# multi-pcb-gps.net
KiCad netlist of a schematic drawn in EAGLE
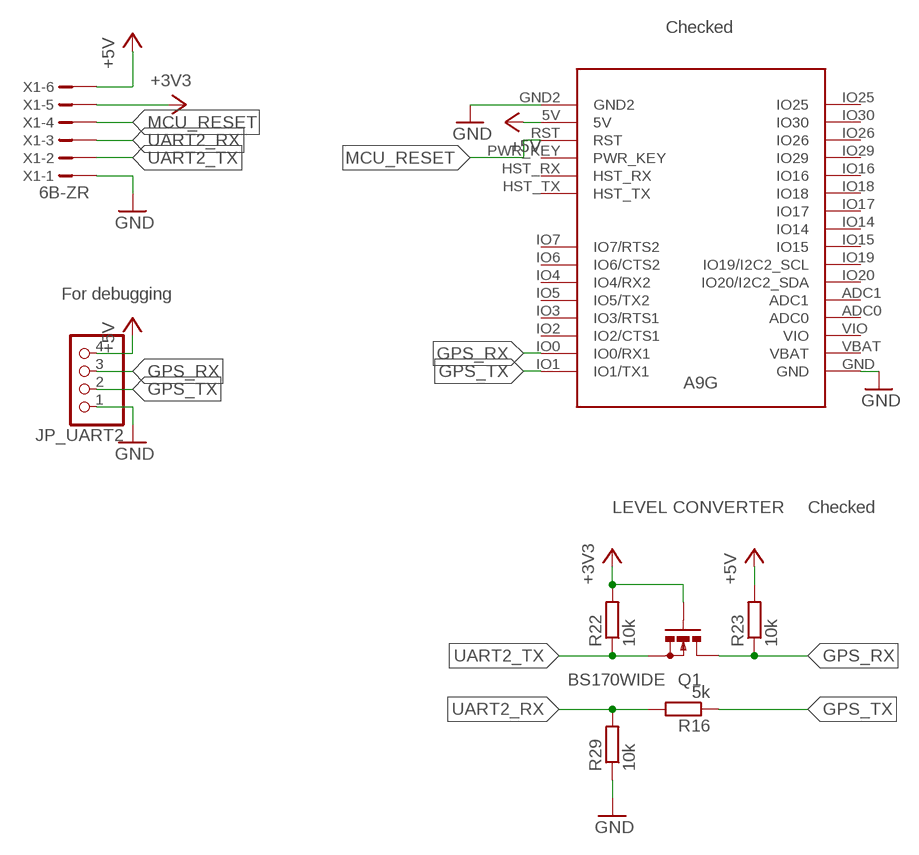
[diagram p0: schematic, sheet 1]

(export (version "E")
  (design (tool "Eeschema 10.0.6"))
  (components
    (comp (ref "JP_UART2")
      (value "PINHD-1X4")
      (footprint "eagle-import:1X04")
      (libsource (lib "eagle-import") (part "PINHD-1X4"))
    )
    (comp (ref "Q1")
      (value "BS170WIDE")
      (footprint "eagle-import:SOT54E2")
      (libsource (lib "eagle-import") (part "BS170WIDE"))
    )
    (comp (ref "R16")
      (value "5k")
      (footprint "eagle-import:0207_7")
      (libsource (lib "eagle-import") (part "R-EU_0207/7"))
    )
    (comp (ref "R22")
      (value "10k")
      (footprint "eagle-import:0207_7")
      (libsource (lib "eagle-import") (part "R-EU_0207/7"))
    )
    (comp (ref "R23")
      (value "10k")
      (footprint "eagle-import:0207_7")
      (libsource (lib "eagle-import") (part "R-EU_0207/7"))
    )
    (comp (ref "R29")
      (value "10k")
      (footprint "eagle-import:0207_7")
      (libsource (lib "eagle-import") (part "R-EU_0207/7"))
    )
    (comp (ref "U$6")
      (value "A9G")
      (footprint "eagle-import:A9G")
      (libsource (lib "eagle-import") (part "A9G"))
    )
    (comp (ref "X1")
      (value "6B-ZR")
      (footprint "eagle-import:B6B-ZR2.5")
      (libsource (lib "eagle-import") (part "?6B-ZR"))
    )
  )
  (nets
    (net (code "1") (name "+3V3") (class "Default")
      (node (ref "Q1") (pin "G") (pinfunction "G_G") (pintype "passive"))
      (node (ref "R22") (pin "2") (pinfunction "2_2") (pintype "passive"))
      (node (ref "X1") (pin "5") (pinfunction "1_5") (pintype "passive"))
    )
    (net (code "2") (name "+5V") (class "Default")
      (node (ref "JP_UART2") (pin "4") (pinfunction "4_4") (pintype "passive"))
      (node (ref "R23") (pin "2") (pinfunction "2_2") (pintype "passive"))
      (node (ref "U$6") (pin "5V") (pinfunction "5V_5V") (pintype "bidirectional"))
      (node (ref "X1") (pin "6") (pinfunction "1_6") (pintype "passive"))
    )
    (net (code "3") (name "GND") (class "Default")
      (node (ref "JP_UART2") (pin "1") (pinfunction "1_1") (pintype "passive"))
      (node (ref "R29") (pin "1") (pinfunction "1_1") (pintype "passive"))
      (node (ref "U$6") (pin "GND") (pinfunction "GND_GND") (pintype "bidirectional"))
      (node (ref "U$6") (pin "GND2") (pinfunction "GND2_GND2") (pintype "bidirectional"))
      (node (ref "X1") (pin "1") (pinfunction "1_1") (pintype "passive"))
    )
    (net (code "4") (name "GPS_RX") (class "Default")
      (node (ref "JP_UART2") (pin "3") (pinfunction "3_3") (pintype "passive"))
      (node (ref "Q1") (pin "D") (pinfunction "D_D") (pintype "passive"))
      (node (ref "R23") (pin "1") (pinfunction "1_1") (pintype "passive"))
      (node (ref "U$6") (pin "IO0") (pinfunction "IO0/RX1_IO0") (pintype "bidirectional"))
    )
    (net (code "5") (name "GPS_TX") (class "Default")
      (node (ref "JP_UART2") (pin "2") (pinfunction "2_2") (pintype "passive"))
      (node (ref "R16") (pin "1") (pinfunction "1_1") (pintype "passive"))
      (node (ref "U$6") (pin "IO1") (pinfunction "IO1/TX1_IO1") (pintype "bidirectional"))
    )
    (net (code "6") (name "MCU_RESET") (class "Default")
      (node (ref "U$6") (pin "RST") (pinfunction "RST_RST") (pintype "bidirectional"))
      (node (ref "X1") (pin "4") (pinfunction "1_4") (pintype "passive"))
    )
    (net (code "7") (name "UART2_RX") (class "Default")
      (node (ref "R16") (pin "2") (pinfunction "2_2") (pintype "passive"))
      (node (ref "R29") (pin "2") (pinfunction "2_2") (pintype "passive"))
      (node (ref "X1") (pin "3") (pinfunction "1_3") (pintype "passive"))
    )
    (net (code "8") (name "UART2_TX") (class "Default")
      (node (ref "Q1") (pin "S") (pinfunction "S_S") (pintype "passive"))
      (node (ref "R22") (pin "1") (pinfunction "1_1") (pintype "passive"))
      (node (ref "X1") (pin "2") (pinfunction "1_2") (pintype "passive"))
    )
    (net (code "9") (name "unconnected-(U$6-IO2{slash}CTS1-PadIO2)") (class "Default")
      (node (ref "U$6") (pin "IO2") (pinfunction "IO2/CTS1_IO2") (pintype "bidirectional"))
    )
    (net (code "10") (name "unconnected-(U$6-IO3{slash}RTS1-PadIO3)") (class "Default")
      (node (ref "U$6") (pin "IO3") (pinfunction "IO3/RTS1_IO3") (pintype "bidirectional"))
    )
    (net (code "11") (name "unconnected-(U$6-IO4{slash}RX2-PadIO4)") (class "Default")
      (node (ref "U$6") (pin "IO4") (pinfunction "IO4/RX2_IO4") (pintype "bidirectional"))
    )
    (net (code "12") (name "unconnected-(U$6-IO5{slash}TX2-PadIO5)") (class "Default")
      (node (ref "U$6") (pin "IO5") (pinfunction "IO5/TX2_IO5") (pintype "bidirectional"))
    )
    (net (code "13") (name "unconnected-(U$6-IO6{slash}CTS2-PadIO6)") (class "Default")
      (node (ref "U$6") (pin "IO6") (pinfunction "IO6/CTS2_IO6") (pintype "bidirectional"))
    )
    (net (code "14") (name "unconnected-(U$6-IO7{slash}RTS2-PadIO7)") (class "Default")
      (node (ref "U$6") (pin "IO7") (pinfunction "IO7/RTS2_IO7") (pintype "bidirectional"))
    )
    (net (code "15") (name "unconnected-(U$6-IO19{slash}I2C2_SCL-PadIO19)") (class "Default")
      (node (ref "U$6") (pin "IO19") (pinfunction "IO19/I2C2_SCL_IO19") (pintype "bidirectional"))
    )
    (net (code "16") (name "unconnected-(U$6-IO20{slash}I2C2_SDA-PadIO20)") (class "Default")
      (node (ref "U$6") (pin "IO20") (pinfunction "IO20/I2C2_SDA_IO20") (pintype "bidirectional"))
    )
    (net (code "17") (name "unconnected-(U$6-PadADC0)") (class "Default")
      (node (ref "U$6") (pin "ADC0") (pinfunction "ADC0_ADC0") (pintype "bidirectional"))
    )
    (net (code "18") (name "unconnected-(U$6-PadADC1)") (class "Default")
      (node (ref "U$6") (pin "ADC1") (pinfunction "ADC1_ADC1") (pintype "bidirectional"))
    )
    (net (code "19") (name "unconnected-(U$6-PadHST_RX)") (class "Default")
      (node (ref "U$6") (pin "HST_RX") (pinfunction "HST_RX_HST_RX") (pintype "bidirectional"))
    )
    (net (code "20") (name "unconnected-(U$6-PadHST_TX)") (class "Default")
      (node (ref "U$6") (pin "HST_TX") (pinfunction "HST_TX_HST_TX") (pintype "bidirectional"))
    )
    (net (code "21") (name "unconnected-(U$6-PadIO14)") (class "Default")
      (node (ref "U$6") (pin "IO14") (pinfunction "IO14_IO14") (pintype "bidirectional"))
    )
    (net (code "22") (name "unconnected-(U$6-PadIO15)") (class "Default")
      (node (ref "U$6") (pin "IO15") (pinfunction "IO15_IO15") (pintype "bidirectional"))
    )
    (net (code "23") (name "unconnected-(U$6-PadIO16)") (class "Default")
      (node (ref "U$6") (pin "IO16") (pinfunction "IO16_IO16") (pintype "bidirectional"))
    )
    (net (code "24") (name "unconnected-(U$6-PadIO17)") (class "Default")
      (node (ref "U$6") (pin "IO17") (pinfunction "IO17_IO17") (pintype "bidirectional"))
    )
    (net (code "25") (name "unconnected-(U$6-PadIO18)") (class "Default")
      (node (ref "U$6") (pin "IO18") (pinfunction "IO18_IO18") (pintype "bidirectional"))
    )
    (net (code "26") (name "unconnected-(U$6-PadIO25)") (class "Default")
      (node (ref "U$6") (pin "IO25") (pinfunction "IO25_IO25") (pintype "bidirectional"))
    )
    (net (code "27") (name "unconnected-(U$6-PadIO26)") (class "Default")
      (node (ref "U$6") (pin "IO26") (pinfunction "IO26_IO26") (pintype "bidirectional"))
    )
    (net (code "28") (name "unconnected-(U$6-PadIO29)") (class "Default")
      (node (ref "U$6") (pin "IO29") (pinfunction "IO29_IO29") (pintype "bidirectional"))
    )
    (net (code "29") (name "unconnected-(U$6-PadIO30)") (class "Default")
      (node (ref "U$6") (pin "IO30") (pinfunction "IO30_IO30") (pintype "bidirectional"))
    )
    (net (code "30") (name "unconnected-(U$6-PadPWR_KEY)") (class "Default")
      (node (ref "U$6") (pin "PWR_KEY") (pinfunction "PWR_KEY_PWR_KEY") (pintype "bidirectional"))
    )
    (net (code "31") (name "unconnected-(U$6-PadVBAT)") (class "Default")
      (node (ref "U$6") (pin "VBAT") (pinfunction "VBAT_VBAT") (pintype "bidirectional"))
    )
    (net (code "32") (name "unconnected-(U$6-PadVIO)") (class "Default")
      (node (ref "U$6") (pin "VIO") (pinfunction "VIO_VIO") (pintype "bidirectional"))
    )
  )
)
